# SoundShield.net
KiCad netlist of a schematic drawn in EAGLE
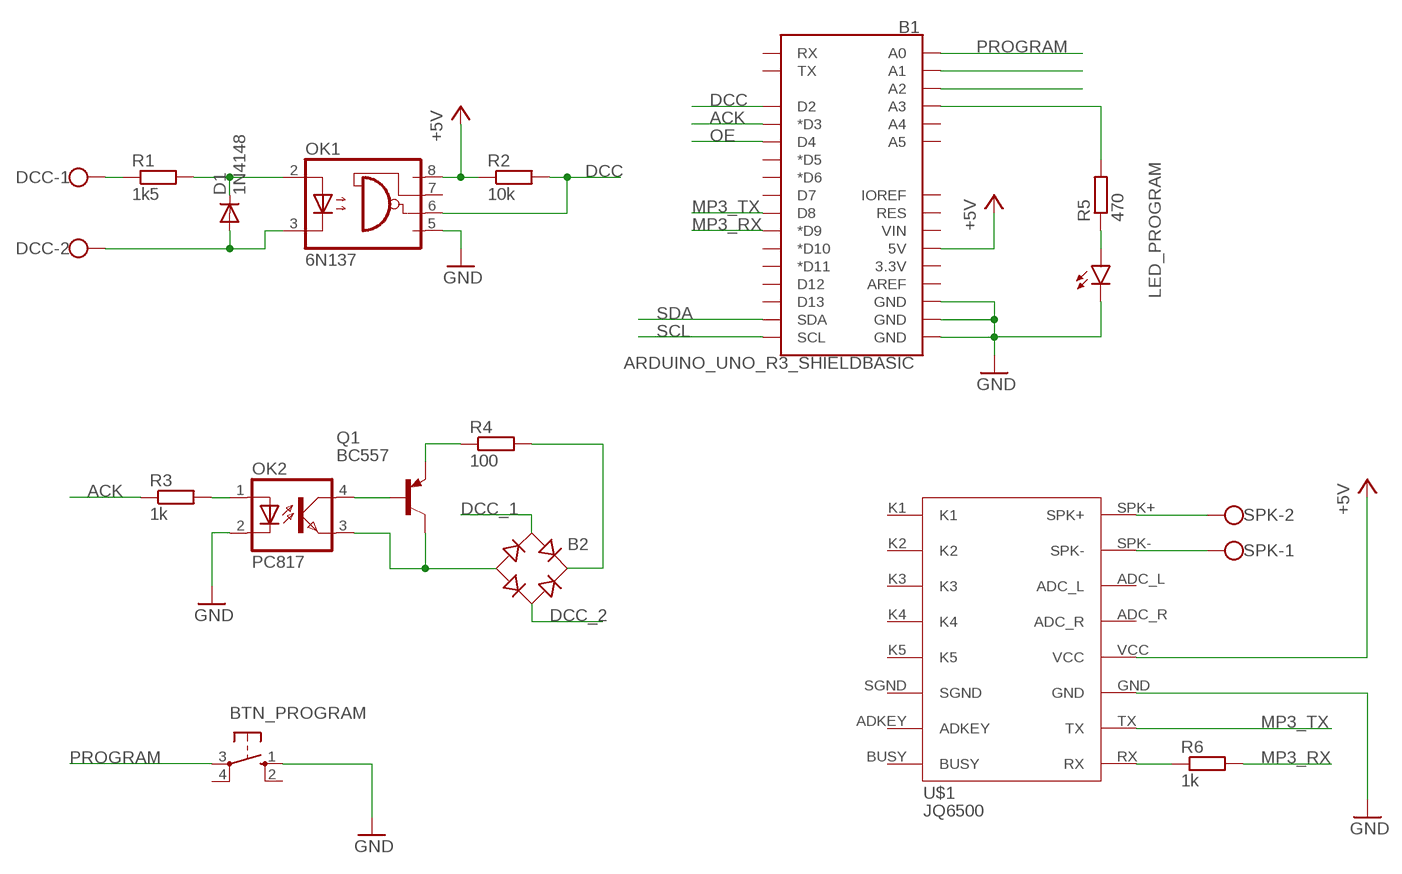
[diagram p0: schematic, sheet 1]

(export (version "E")
  (design (tool "Eeschema 10.0.6"))
  (components
    (comp (ref "B1")
      (value "ARDUINO_UNO_R3_SHIELDBASIC")
      (footprint "eagle-import:UNO_R3_SHIELD")
      (libsource (lib "eagle-import") (part "ARDUINO_UNO_R3_SHIELDBASIC"))
    )
    (comp (ref "B2")
      (value "RB1A")
      (footprint "eagle-import:RB1A")
      (libsource (lib "eagle-import") (part "RB1A"))
    )
    (comp (ref "BTN_PROGRAM")
      (value "10-XX")
      (footprint "eagle-import:B3F-10XX")
      (fields (field (name "MPN") "B3F-1000"))
      (libsource (lib "eagle-import") (part "10-XX"))
    )
    (comp (ref "D1")
      (value "1N4148")
      (footprint "eagle-import:DO35-7")
      (libsource (lib "eagle-import") (part "1N4148DO35-7"))
    )
    (comp (ref "DCC")
      (value "W237-102")
      (footprint "eagle-import:W237-102")
      (fields (field (name "MPN") "237-102"))
      (libsource (lib "eagle-import") (part "W237-102"))
    )
    (comp (ref "LED_PROGRAM")
      (value "LED3MM")
      (footprint "eagle-import:LED3MM")
      (libsource (lib "eagle-import") (part "LED3MM"))
    )
    (comp (ref "OK1")
      (value "6N137")
      (footprint "eagle-import:DIL08")
      (libsource (lib "eagle-import") (part "6N137"))
    )
    (comp (ref "OK2")
      (value "PC817")
      (footprint "eagle-import:DIL04")
      (fields (field (name "MPN") "PC817X4J000F"))
      (libsource (lib "eagle-import") (part "PC817"))
    )
    (comp (ref "Q1")
      (value "BC557")
      (footprint "eagle-import:TO92")
      (libsource (lib "eagle-import") (part "BC557"))
    )
    (comp (ref "R1")
      (value "1k5")
      (footprint "eagle-import:0207_2V")
      (libsource (lib "eagle-import") (part "R-EU_0207/2V"))
    )
    (comp (ref "R2")
      (value "10k")
      (footprint "eagle-import:0207_2V")
      (libsource (lib "eagle-import") (part "R-EU_0207/2V"))
    )
    (comp (ref "R3")
      (value "1k")
      (footprint "eagle-import:0207_2V")
      (libsource (lib "eagle-import") (part "R-EU_0207/2V"))
    )
    (comp (ref "R4")
      (value "100")
      (footprint "eagle-import:0207_2V")
      (libsource (lib "eagle-import") (part "R-EU_0207/2V"))
    )
    (comp (ref "R5")
      (value "470")
      (footprint "eagle-import:0207_2V")
      (libsource (lib "eagle-import") (part "R-EU_0207/2V"))
    )
    (comp (ref "R6")
      (value "1k")
      (footprint "eagle-import:0207_2V")
      (libsource (lib "eagle-import") (part "R-EU_0207/2V"))
    )
    (comp (ref "SPK")
      (value "W237-102")
      (footprint "eagle-import:W237-102")
      (fields (field (name "MPN") "237-102"))
      (libsource (lib "eagle-import") (part "W237-102"))
    )
    (comp (ref "U$1")
      (value "JQ6500")
      (footprint "eagle-import:JQ6500-PACKAGE")
      (libsource (lib "eagle-import") (part "JQ6500"))
    )
  )
  (nets
    (net (code "1") (name "+5V") (class "Default")
      (node (ref "B1") (pin "5V") (pinfunction "5V_5V") (pintype "bidirectional"))
      (node (ref "OK1") (pin "8") (pinfunction "VCC_8") (pintype "passive"))
      (node (ref "R2") (pin "1") (pinfunction "1_1") (pintype "passive"))
      (node (ref "U$1") (pin "VCC") (pinfunction "VCC_VCC") (pintype "bidirectional"))
    )
    (net (code "2") (name "/ACK") (class "Default")
      (node (ref "B1") (pin "D3") (pinfunction "*D3_D3") (pintype "bidirectional"))
      (node (ref "R3") (pin "1") (pinfunction "1_1") (pintype "passive"))
    )
    (net (code "3") (name "/DCC") (class "Default")
      (node (ref "B1") (pin "D2") (pinfunction "D2_D2") (pintype "bidirectional"))
      (node (ref "OK1") (pin "6") (pinfunction "VO_6") (pintype "passive"))
      (node (ref "R2") (pin "2") (pinfunction "2_2") (pintype "passive"))
    )
    (net (code "4") (name "/DCC_1") (class "Default")
      (node (ref "B2") (pin "AC1") (pinfunction "AC1_AC1") (pintype "passive"))
      (node (ref "DCC") (pin "1") (pinfunction "KL_1") (pintype "passive"))
      (node (ref "R1") (pin "1") (pinfunction "1_1") (pintype "passive"))
    )
    (net (code "5") (name "/DCC_2") (class "Default")
      (node (ref "B2") (pin "AC2") (pinfunction "AC2_AC2") (pintype "passive"))
      (node (ref "D1") (pin "A") (pinfunction "A_A") (pintype "passive"))
      (node (ref "DCC") (pin "2") (pinfunction "KL_2") (pintype "passive"))
      (node (ref "OK1") (pin "3") (pinfunction "C_3") (pintype "passive"))
    )
    (net (code "6") (name "/MP3_RX") (class "Default")
      (node (ref "B1") (pin "D9") (pinfunction "*D9_D9") (pintype "bidirectional"))
      (node (ref "R6") (pin "2") (pinfunction "2_2") (pintype "passive"))
    )
    (net (code "7") (name "/MP3_TX") (class "Default")
      (node (ref "B1") (pin "D8") (pinfunction "D8_D8") (pintype "bidirectional"))
      (node (ref "U$1") (pin "TX") (pinfunction "TX_TX") (pintype "bidirectional"))
    )
    (net (code "8") (name "/OE") (class "Default")
      (node (ref "B1") (pin "D4") (pinfunction "D4_D4") (pintype "bidirectional"))
    )
    (net (code "9") (name "/PROGRAM") (class "Default")
      (node (ref "B1") (pin "A0") (pinfunction "A0_A0") (pintype "bidirectional"))
      (node (ref "BTN_PROGRAM") (pin "3") (pinfunction "P_3") (pintype "passive"))
    )
    (net (code "10") (name "/SCL") (class "Default")
      (node (ref "B1") (pin "SCL") (pinfunction "SCL_SCL") (pintype "bidirectional"))
    )
    (net (code "11") (name "/SDA") (class "Default")
      (node (ref "B1") (pin "SDA") (pinfunction "SDA_SDA") (pintype "bidirectional"))
    )
    (net (code "12") (name "GND") (class "Default")
      (node (ref "B1") (pin "GND@0") (pinfunction "GND_GND@0") (pintype "bidirectional"))
      (node (ref "B1") (pin "GND@1") (pinfunction "GND_GND@1") (pintype "bidirectional"))
      (node (ref "B1") (pin "GND@2") (pinfunction "GND_GND@2") (pintype "bidirectional"))
      (node (ref "BTN_PROGRAM") (pin "1") (pinfunction "S_1") (pintype "passive"))
      (node (ref "LED_PROGRAM") (pin "K") (pinfunction "C_K") (pintype "passive"))
      (node (ref "OK1") (pin "5") (pinfunction "GND_5") (pintype "passive"))
      (node (ref "OK2") (pin "2") (pinfunction "C_2") (pintype "passive"))
      (node (ref "U$1") (pin "GND") (pinfunction "GND_GND") (pintype "bidirectional"))
    )
    (net (code "13") (name "Net-(B1-PadA3)") (class "Default")
      (node (ref "B1") (pin "A3") (pinfunction "A3_A3") (pintype "bidirectional"))
      (node (ref "R5") (pin "2") (pinfunction "2_2") (pintype "passive"))
    )
    (net (code "14") (name "Net-(B2-Pad+)") (class "Default")
      (node (ref "B2") (pin "+") (pinfunction "+_+") (pintype "passive"))
      (node (ref "R4") (pin "2") (pinfunction "2_2") (pintype "passive"))
    )
    (net (code "15") (name "Net-(LED_PROGRAM-PadA)") (class "Default")
      (node (ref "LED_PROGRAM") (pin "A") (pinfunction "A_A") (pintype "passive"))
      (node (ref "R5") (pin "1") (pinfunction "1_1") (pintype "passive"))
    )
    (net (code "16") (name "Net-(OK1-A)") (class "Default")
      (node (ref "D1") (pin "C") (pinfunction "C_C") (pintype "passive"))
      (node (ref "OK1") (pin "2") (pinfunction "A_2") (pintype "passive"))
      (node (ref "R1") (pin "2") (pinfunction "2_2") (pintype "passive"))
    )
    (net (code "17") (name "Net-(OK2-A)") (class "Default")
      (node (ref "OK2") (pin "1") (pinfunction "A_1") (pintype "passive"))
      (node (ref "R3") (pin "2") (pinfunction "2_2") (pintype "passive"))
    )
    (net (code "18") (name "Net-(OK2-COL)") (class "Default")
      (node (ref "OK2") (pin "4") (pinfunction "COL_4") (pintype "passive"))
      (node (ref "Q1") (pin "2") (pinfunction "B_2") (pintype "passive"))
    )
    (net (code "19") (name "Net-(OK2-EMIT)") (class "Default")
      (node (ref "B2") (pin "-") (pinfunction "-_-") (pintype "passive"))
      (node (ref "OK2") (pin "3") (pinfunction "EMIT_3") (pintype "passive"))
      (node (ref "Q1") (pin "3") (pinfunction "C_3") (pintype "passive"))
    )
    (net (code "20") (name "Net-(Q1-E)") (class "Default")
      (node (ref "Q1") (pin "1") (pinfunction "E_1") (pintype "passive"))
      (node (ref "R4") (pin "1") (pinfunction "1_1") (pintype "passive"))
    )
    (net (code "21") (name "Net-(R6-Pad1)") (class "Default")
      (node (ref "R6") (pin "1") (pinfunction "1_1") (pintype "passive"))
      (node (ref "U$1") (pin "RX") (pinfunction "RX_RX") (pintype "bidirectional"))
    )
    (net (code "22") (name "Net-(SPKA-KL)") (class "Default")
      (node (ref "SPK") (pin "1") (pinfunction "KL_1") (pintype "passive"))
      (node (ref "U$1") (pin "SPK-") (pinfunction "SPK-_SPK-") (pintype "bidirectional"))
    )
    (net (code "23") (name "Net-(SPKB-KL)") (class "Default")
      (node (ref "SPK") (pin "2") (pinfunction "KL_2") (pintype "passive"))
      (node (ref "U$1") (pin "SPK+") (pinfunction "SPK+_SPK+") (pintype "bidirectional"))
    )
    (net (code "24") (name "unconnected-(B1-*D5-PadD5)") (class "Default")
      (node (ref "B1") (pin "D5") (pinfunction "*D5_D5") (pintype "bidirectional"))
    )
    (net (code "25") (name "unconnected-(B1-*D6-PadD6)") (class "Default")
      (node (ref "B1") (pin "D6") (pinfunction "*D6_D6") (pintype "bidirectional"))
    )
    (net (code "26") (name "unconnected-(B1-*D10-PadD10)") (class "Default")
      (node (ref "B1") (pin "D10") (pinfunction "*D10_D10") (pintype "bidirectional"))
    )
    (net (code "27") (name "unconnected-(B1-*D11-PadD11)") (class "Default")
      (node (ref "B1") (pin "D11") (pinfunction "*D11_D11") (pintype "bidirectional"))
    )
    (net (code "28") (name "unconnected-(B1-Pad3.3V)") (class "Default")
      (node (ref "B1") (pin "3.3V") (pinfunction "3.3V_3.3V") (pintype "bidirectional"))
    )
    (net (code "29") (name "unconnected-(B1-PadA1)") (class "Default")
      (node (ref "B1") (pin "A1") (pinfunction "A1_A1") (pintype "bidirectional"))
    )
    (net (code "30") (name "unconnected-(B1-PadA2)") (class "Default")
      (node (ref "B1") (pin "A2") (pinfunction "A2_A2") (pintype "bidirectional"))
    )
    (net (code "31") (name "unconnected-(B1-PadA4)") (class "Default")
      (node (ref "B1") (pin "A4") (pinfunction "A4_A4") (pintype "bidirectional"))
    )
    (net (code "32") (name "unconnected-(B1-PadA5)") (class "Default")
      (node (ref "B1") (pin "A5") (pinfunction "A5_A5") (pintype "bidirectional"))
    )
    (net (code "33") (name "unconnected-(B1-PadAREF)") (class "Default")
      (node (ref "B1") (pin "AREF") (pinfunction "AREF_AREF") (pintype "bidirectional"))
    )
    (net (code "34") (name "unconnected-(B1-PadD7)") (class "Default")
      (node (ref "B1") (pin "D7") (pinfunction "D7_D7") (pintype "bidirectional"))
    )
    (net (code "35") (name "unconnected-(B1-PadD12)") (class "Default")
      (node (ref "B1") (pin "D12") (pinfunction "D12_D12") (pintype "bidirectional"))
    )
    (net (code "36") (name "unconnected-(B1-PadD13)") (class "Default")
      (node (ref "B1") (pin "D13") (pinfunction "D13_D13") (pintype "bidirectional"))
    )
    (net (code "37") (name "unconnected-(B1-PadIOREF)") (class "Default")
      (node (ref "B1") (pin "IOREF") (pinfunction "IOREF_IOREF") (pintype "bidirectional"))
    )
    (net (code "38") (name "unconnected-(B1-PadRES)") (class "Default")
      (node (ref "B1") (pin "RES") (pinfunction "RES_RES") (pintype "bidirectional"))
    )
    (net (code "39") (name "unconnected-(B1-PadRX)") (class "Default")
      (node (ref "B1") (pin "RX") (pinfunction "RX_RX") (pintype "bidirectional"))
    )
    (net (code "40") (name "unconnected-(B1-PadTX)") (class "Default")
      (node (ref "B1") (pin "TX") (pinfunction "TX_TX") (pintype "bidirectional"))
    )
    (net (code "41") (name "unconnected-(B1-PadVIN)") (class "Default")
      (node (ref "B1") (pin "VIN") (pinfunction "VIN_VIN") (pintype "bidirectional"))
    )
    (net (code "42") (name "unconnected-(BTN_PROGRAM-P1-Pad4)") (class "Default")
      (node (ref "BTN_PROGRAM") (pin "4") (pinfunction "P1_4") (pintype "passive"))
    )
    (net (code "43") (name "unconnected-(BTN_PROGRAM-S1-Pad2)") (class "Default")
      (node (ref "BTN_PROGRAM") (pin "2") (pinfunction "S1_2") (pintype "passive"))
    )
    (net (code "44") (name "unconnected-(OK1-VE-Pad7)") (class "Default")
      (node (ref "OK1") (pin "7") (pinfunction "VE_7") (pintype "passive"))
    )
    (net (code "45") (name "unconnected-(U$1-PadADC_L)") (class "Default")
      (node (ref "U$1") (pin "ADC_L") (pinfunction "ADC_L_ADC_L") (pintype "bidirectional"))
    )
    (net (code "46") (name "unconnected-(U$1-PadADC_R)") (class "Default")
      (node (ref "U$1") (pin "ADC_R") (pinfunction "ADC_R_ADC_R") (pintype "bidirectional"))
    )
    (net (code "47") (name "unconnected-(U$1-PadADKEY)") (class "Default")
      (node (ref "U$1") (pin "ADKEY") (pinfunction "ADKEY_ADKEY") (pintype "bidirectional"))
    )
    (net (code "48") (name "unconnected-(U$1-PadBUSY)") (class "Default")
      (node (ref "U$1") (pin "BUSY") (pinfunction "BUSY_BUSY") (pintype "bidirectional"))
    )
    (net (code "49") (name "unconnected-(U$1-PadK1)") (class "Default")
      (node (ref "U$1") (pin "K1") (pinfunction "K1_K1") (pintype "bidirectional"))
    )
    (net (code "50") (name "unconnected-(U$1-PadK2)") (class "Default")
      (node (ref "U$1") (pin "K2") (pinfunction "K2_K2") (pintype "bidirectional"))
    )
    (net (code "51") (name "unconnected-(U$1-PadK3)") (class "Default")
      (node (ref "U$1") (pin "K3") (pinfunction "K3_K3") (pintype "bidirectional"))
    )
    (net (code "52") (name "unconnected-(U$1-PadK4)") (class "Default")
      (node (ref "U$1") (pin "K4") (pinfunction "K4_K4") (pintype "bidirectional"))
    )
    (net (code "53") (name "unconnected-(U$1-PadK5)") (class "Default")
      (node (ref "U$1") (pin "K5") (pinfunction "K5_K5") (pintype "bidirectional"))
    )
    (net (code "54") (name "unconnected-(U$1-PadSGND)") (class "Default")
      (node (ref "U$1") (pin "SGND") (pinfunction "SGND_SGND") (pintype "bidirectional"))
    )
  )
)
